# LED_Sheet.net
KiCad netlist of a schematic drawn in Altium Designer
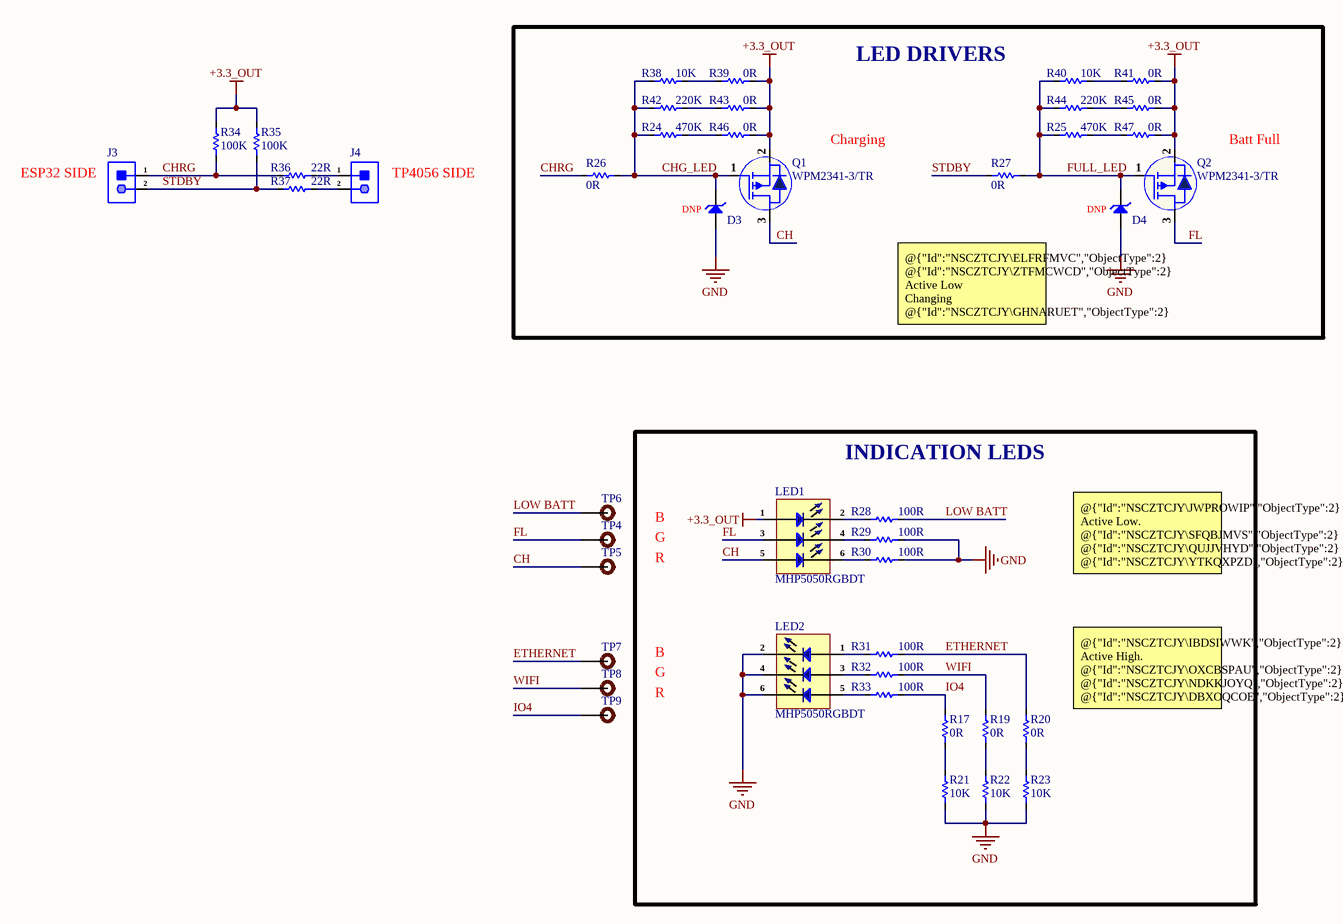
[diagram p0: LED_Sheet.SchDoc]

(export (version "E")
  (design (tool "Eeschema 10.0.6"))
  (components
    (comp (ref "D3")
      (value "MM3Z3V3")
      (footprint "SOD-323")
      (description "±5% Single 3.1V~3.5V 300mW 3.3V SOD-323 Zener Diodes ROHS")
      (fields (field (name "MANUFACTURER") "JSMSEMI") (field (name "LCSC PART NUMBER") "C123917"))
      (libsource (lib "eSpark Libraries") (part "MM3Z3V3"))
    )
    (comp (ref "D4")
      (value "MM3Z3V3")
      (footprint "SOD-323")
      (description "±5% Single 3.1V~3.5V 300mW 3.3V SOD-323 Zener Diodes ROHS")
      (fields (field (name "MANUFACTURER") "JSMSEMI") (field (name "LCSC PART NUMBER") "C123917"))
      (libsource (lib "eSpark Libraries") (part "MM3Z3V3"))
    )
    (comp (ref "J3")
      (value "826629-2")
      (footprint "HDR1X2_")
      (description "CONN HEADER VERT 2POS 2.54MM")
      (fields
        (field (name "MANUFACTURER") "TE Connectivity")
        (field (name "MANUFACTURER PART NUMBER") "8266292")
      )
      (libsource (lib "") (part "826629-2_1"))
    )
    (comp (ref "J4")
      (value "826629-2")
      (footprint "HDR1X2_")
      (description "CONN HEADER VERT 2POS 2.54MM")
      (fields
        (field (name "MANUFACTURER") "TE Connectivity")
        (field (name "MANUFACTURER PART NUMBER") "8266292")
      )
      (libsource (lib "eSpark Libraries") (part "826629-2"))
    )
    (comp (ref "LED1")
      (value "MHP5050RGBDT")
      (footprint "MHP5050RGBDT")
      (description "20mA White Diffused -40℃~+85℃ RGB SMD5050 Light Emitting Diodes (LED) ROHS")
      (fields (field (name "MANUFACTURER") "MEIHUA") (field (name "LCSC PART NUMBER") "C409780"))
      (libsource (lib "eSpark Libraries") (part "MHP5050RGBDT"))
    )
    (comp (ref "LED2")
      (value "MHP5050RGBDT")
      (footprint "MHP5050RGBDT")
      (description "20mA White Diffused -40℃~+85℃ RGB SMD5050 Light Emitting Diodes (LED) ROHS")
      (fields (field (name "MANUFACTURER") "MEIHUA") (field (name "LCSC PART NUMBER") "C409780"))
      (libsource (lib "") (part "MHP5050RGBDT_1"))
    )
    (comp (ref "Q1")
      (value "WPM2341-3/TR")
      (footprint "Sot-23")
      (description "20V 3.5A 750mW 61mΩ@4.5V,3.3A 1V@250uA 1PCSPChannel SOT-23 MOSFETs ROHS")
      (fields (field (name "MANUFACTURER") "WILLSEMI") (field (name "LCSC PART NUMBER") "C167138"))
      (libsource (lib "eSpark Libraries") (part "WPM2341-3/TR"))
    )
    (comp (ref "Q2")
      (value "WPM2341-3/TR")
      (footprint "Sot-23")
      (description "20V 3.5A 750mW 61mΩ@4.5V,3.3A 1V@250uA 1PCSPChannel SOT-23 MOSFETs ROHS")
      (fields (field (name "MANUFACTURER") "WILLSEMI") (field (name "LCSC PART NUMBER") "C167138"))
      (libsource (lib "eSpark Libraries") (part "WPM2341-3/TR"))
    )
    (comp (ref "R17")
      (value "0R")
      (footprint "Res-0402")
      (description "RESISTOR 0402 JUMPER ZERO OHM")
      (fields
        (field (name "MANUFACTURER") "Yageo")
        (field (name "MANUFACTURER PART NUMBER") "AC0402FR-070RL")
      )
      (libsource (lib "eSpark Libraries") (part "AC0402FR-070RL"))
    )
    (comp (ref "R19")
      (value "0R")
      (footprint "Res-0402")
      (description "RESISTOR 0402 JUMPER ZERO OHM")
      (fields
        (field (name "MANUFACTURER") "Yageo")
        (field (name "MANUFACTURER PART NUMBER") "AC0402FR-070RL")
      )
      (libsource (lib "eSpark Libraries") (part "AC0402FR-070RL"))
    )
    (comp (ref "R20")
      (value "0R")
      (footprint "Res-0402")
      (description "RESISTOR 0402 JUMPER ZERO OHM")
      (fields
        (field (name "MANUFACTURER") "Yageo")
        (field (name "MANUFACTURER PART NUMBER") "AC0402FR-070RL")
      )
      (libsource (lib "eSpark Libraries") (part "AC0402FR-070RL"))
    )
    (comp (ref "R21")
      (value "10K")
      (footprint "Res-0402")
      (description "RES 10K OHM 1% 1/16W 0402")
      (fields
        (field (name "MANUFACTURER") "Yageo")
        (field (name "MANUFACTURER PART NUMBER") "RC0402FR-0710KL")
      )
      (libsource (lib "eSpark Libraries") (part "RC0402FR-0710KL"))
    )
    (comp (ref "R22")
      (value "10K")
      (footprint "Res-0402")
      (description "RES 10K OHM 1% 1/16W 0402")
      (fields
        (field (name "MANUFACTURER") "Yageo")
        (field (name "MANUFACTURER PART NUMBER") "RC0402FR-0710KL")
      )
      (libsource (lib "eSpark Libraries") (part "RC0402FR-0710KL"))
    )
    (comp (ref "R23")
      (value "10K")
      (footprint "Res-0402")
      (description "RES 10K OHM 1% 1/16W 0402")
      (fields
        (field (name "MANUFACTURER") "Yageo")
        (field (name "MANUFACTURER PART NUMBER") "RC0402FR-0710KL")
      )
      (libsource (lib "eSpark Libraries") (part "RC0402FR-0710KL"))
    )
    (comp (ref "R24")
      (value "470K")
      (footprint "Res-0402")
      (description "RES 470K OHM 1% 1/16W 0402")
      (fields
        (field (name "MANUFACTURER") "Yageo")
        (field (name "MANUFACTURER PART NUMBER") "RC0402FR-07470KL")
      )
      (libsource (lib "eSpark Libraries") (part "RC0402FR-07470KL"))
    )
    (comp (ref "R25")
      (value "470K")
      (footprint "Res-0402")
      (description "RES 470K OHM 1% 1/16W 0402")
      (fields
        (field (name "MANUFACTURER") "Yageo")
        (field (name "MANUFACTURER PART NUMBER") "RC0402FR-07470KL")
      )
      (libsource (lib "eSpark Libraries") (part "RC0402FR-07470KL"))
    )
    (comp (ref "R26")
      (value "0R")
      (footprint "Res-0402")
      (description "RES 0 OHM JUMPER 1/16W 0402")
      (fields
        (field (name "MANUFACTURER") "Yageo")
        (field (name "MANUFACTURER PART NUMBER") "RC0402FR-070RL")
      )
      (libsource (lib "eSpark Libraries") (part "RC0402FR-070RL"))
    )
    (comp (ref "R27")
      (value "0R")
      (footprint "Res-0402")
      (description "RES 0 OHM JUMPER 1/16W 0402")
      (fields
        (field (name "MANUFACTURER") "Yageo")
        (field (name "MANUFACTURER PART NUMBER") "RC0402FR-070RL")
      )
      (libsource (lib "eSpark Libraries") (part "RC0402FR-070RL"))
    )
    (comp (ref "R28")
      (value "100R")
      (footprint "Res-0402")
      (description "RES 100 OHM 1% 1/16W 0402")
      (fields
        (field (name "MANUFACTURER") "Yageo")
        (field (name "MANUFACTURER PART NUMBER") "RC0402FR-07100RL")
      )
      (libsource (lib "eSpark Libraries") (part "RC0402FR-07100RL"))
    )
    (comp (ref "R29")
      (value "100R")
      (footprint "Res-0402")
      (description "RES 100 OHM 1% 1/16W 0402")
      (fields
        (field (name "MANUFACTURER") "Yageo")
        (field (name "MANUFACTURER PART NUMBER") "RC0402FR-07100RL")
      )
      (libsource (lib "eSpark Libraries") (part "RC0402FR-07100RL"))
    )
    (comp (ref "R30")
      (value "100R")
      (footprint "Res-0402")
      (description "RES 100 OHM 1% 1/16W 0402")
      (fields
        (field (name "MANUFACTURER") "Yageo")
        (field (name "MANUFACTURER PART NUMBER") "RC0402FR-07100RL")
      )
      (libsource (lib "eSpark Libraries") (part "RC0402FR-07100RL"))
    )
    (comp (ref "R31")
      (value "100R")
      (footprint "Res-0402")
      (description "RES 100 OHM 1% 1/16W 0402")
      (fields
        (field (name "MANUFACTURER") "Yageo")
        (field (name "MANUFACTURER PART NUMBER") "RC0402FR-07100RL")
      )
      (libsource (lib "eSpark Libraries") (part "RC0402FR-07100RL"))
    )
    (comp (ref "R32")
      (value "100R")
      (footprint "Res-0402")
      (description "RES 100 OHM 1% 1/16W 0402")
      (fields
        (field (name "MANUFACTURER") "Yageo")
        (field (name "MANUFACTURER PART NUMBER") "RC0402FR-07100RL")
      )
      (libsource (lib "eSpark Libraries") (part "RC0402FR-07100RL"))
    )
    (comp (ref "R33")
      (value "100R")
      (footprint "Res-0402")
      (description "RES 100 OHM 1% 1/16W 0402")
      (fields
        (field (name "MANUFACTURER") "Yageo")
        (field (name "MANUFACTURER PART NUMBER") "RC0402FR-07100RL")
      )
      (libsource (lib "eSpark Libraries") (part "RC0402FR-07100RL"))
    )
    (comp (ref "R34")
      (value "100K")
      (footprint "Res-0402")
      (description "RES 100K OHM 1% 1/16W 0402")
      (fields
        (field (name "MANUFACTURER") "Yageo")
        (field (name "MANUFACTURER PART NUMBER") "RC0402FR-07100KL")
      )
      (libsource (lib "eSpark Libraries") (part "RC0402FR-07100KL"))
    )
    (comp (ref "R35")
      (value "100K")
      (footprint "Res-0402")
      (description "RES 100K OHM 1% 1/16W 0402")
      (fields
        (field (name "MANUFACTURER") "Yageo")
        (field (name "MANUFACTURER PART NUMBER") "RC0402FR-07100KL")
      )
      (libsource (lib "eSpark Libraries") (part "RC0402FR-07100KL"))
    )
    (comp (ref "R36")
      (value "22R")
      (footprint "Res-0402")
      (description "RES 22 OHM 1% 1/16W 0402")
      (fields
        (field (name "MANUFACTURER") "Yageo")
        (field (name "MANUFACTURER PART NUMBER") "RC0402FR-0722RL")
      )
      (libsource (lib "eSpark Libraries") (part "RC0402FR-0722RL"))
    )
    (comp (ref "R37")
      (value "22R")
      (footprint "Res-0402")
      (description "RES 22 OHM 1% 1/16W 0402")
      (fields
        (field (name "MANUFACTURER") "Yageo")
        (field (name "MANUFACTURER PART NUMBER") "RC0402FR-0722RL")
      )
      (libsource (lib "eSpark Libraries") (part "RC0402FR-0722RL"))
    )
    (comp (ref "R38")
      (value "10K")
      (footprint "Res-0402")
      (description "RES 10K OHM 1% 1/16W 0402")
      (fields
        (field (name "MANUFACTURER") "Yageo")
        (field (name "MANUFACTURER PART NUMBER") "RC0402FR-0710KL")
      )
      (libsource (lib "eSpark Libraries") (part "RC0402FR-0710KL"))
    )
    (comp (ref "R39")
      (value "0R")
      (footprint "Res-0402")
      (description "RESISTOR 0402 JUMPER ZERO OHM")
      (fields
        (field (name "MANUFACTURER") "Yageo")
        (field (name "MANUFACTURER PART NUMBER") "AC0402FR-070RL")
      )
      (libsource (lib "eSpark Libraries") (part "AC0402FR-070RL"))
    )
    (comp (ref "R40")
      (value "10K")
      (footprint "Res-0402")
      (description "RES 10K OHM 1% 1/16W 0402")
      (fields
        (field (name "MANUFACTURER") "Yageo")
        (field (name "MANUFACTURER PART NUMBER") "RC0402FR-0710KL")
      )
      (libsource (lib "eSpark Libraries") (part "RC0402FR-0710KL"))
    )
    (comp (ref "R41")
      (value "0R")
      (footprint "Res-0402")
      (description "RESISTOR 0402 JUMPER ZERO OHM")
      (fields
        (field (name "MANUFACTURER") "Yageo")
        (field (name "MANUFACTURER PART NUMBER") "AC0402FR-070RL")
      )
      (libsource (lib "eSpark Libraries") (part "AC0402FR-070RL"))
    )
    (comp (ref "R42")
      (value "220K")
      (footprint "Res-0402")
      (description "RES 220K OHM 1% 1/16W 0402")
      (fields
        (field (name "MANUFACTURER") "Yageo")
        (field (name "MANUFACTURER PART NUMBER") "RC0402FR-07220KL")
      )
      (libsource (lib "eSpark Libraries") (part "RC0402FR-07220KL"))
    )
    (comp (ref "R43")
      (value "0R")
      (footprint "Res-0402")
      (description "RESISTOR 0402 JUMPER ZERO OHM")
      (fields
        (field (name "MANUFACTURER") "Yageo")
        (field (name "MANUFACTURER PART NUMBER") "AC0402FR-070RL")
      )
      (libsource (lib "eSpark Libraries") (part "AC0402FR-070RL"))
    )
    (comp (ref "R44")
      (value "220K")
      (footprint "Res-0402")
      (description "RES 220K OHM 1% 1/16W 0402")
      (fields
        (field (name "MANUFACTURER") "Yageo")
        (field (name "MANUFACTURER PART NUMBER") "RC0402FR-07220KL")
      )
      (libsource (lib "eSpark Libraries") (part "RC0402FR-07220KL"))
    )
    (comp (ref "R45")
      (value "0R")
      (footprint "Res-0402")
      (description "RESISTOR 0402 JUMPER ZERO OHM")
      (fields
        (field (name "MANUFACTURER") "Yageo")
        (field (name "MANUFACTURER PART NUMBER") "AC0402FR-070RL")
      )
      (libsource (lib "eSpark Libraries") (part "AC0402FR-070RL"))
    )
    (comp (ref "R46")
      (value "0R")
      (footprint "Res-0402")
      (description "RESISTOR 0402 JUMPER ZERO OHM")
      (fields
        (field (name "MANUFACTURER") "Yageo")
        (field (name "MANUFACTURER PART NUMBER") "AC0402FR-070RL")
      )
      (libsource (lib "eSpark Libraries") (part "AC0402FR-070RL"))
    )
    (comp (ref "R47")
      (value "0R")
      (footprint "Res-0402")
      (description "RESISTOR 0402 JUMPER ZERO OHM")
      (fields
        (field (name "MANUFACTURER") "Yageo")
        (field (name "MANUFACTURER PART NUMBER") "AC0402FR-070RL")
      )
      (libsource (lib "eSpark Libraries") (part "AC0402FR-070RL"))
    )
    (comp (ref "TP4")
      (value "TEST POINT 0.5mm Dia")
      (footprint "Test-point - 0.5mm")
      (description "Test Point ON")
      (libsource (lib "eSpark Libraries") (part "TEST POINT 0.5mm Dia"))
    )
    (comp (ref "TP5")
      (value "TEST POINT 0.5mm Dia")
      (footprint "Test-point - 0.5mm")
      (description "Test Point ON")
      (libsource (lib "eSpark Libraries") (part "TEST POINT 0.5mm Dia"))
    )
    (comp (ref "TP6")
      (value "TEST POINT 0.5mm Dia")
      (footprint "Test-point - 0.5mm")
      (description "Test Point ON")
      (libsource (lib "eSpark Libraries") (part "TEST POINT 0.5mm Dia"))
    )
    (comp (ref "TP7")
      (value "TEST POINT 0.5mm Dia")
      (footprint "Test-point - 0.5mm")
      (description "Test Point ON")
      (libsource (lib "eSpark Libraries") (part "TEST POINT 0.5mm Dia"))
    )
    (comp (ref "TP8")
      (value "TEST POINT 0.5mm Dia")
      (footprint "Test-point - 0.5mm")
      (description "Test Point ON")
      (libsource (lib "eSpark Libraries") (part "TEST POINT 0.5mm Dia"))
    )
    (comp (ref "TP9")
      (value "TEST POINT 0.5mm Dia")
      (footprint "Test-point - 0.5mm")
      (description "Test Point ON")
      (libsource (lib "eSpark Libraries") (part "TEST POINT 0.5mm Dia"))
    )
  )
  (nets
    (net (code "1") (name "+3.3_OUT") (class "Default")
      (node (ref "LED1") (pin "1") (pinfunction "1_1") (pintype "passive"))
      (node (ref "Q1") (pin "2") (pinfunction "S_2") (pintype "passive"))
      (node (ref "Q2") (pin "2") (pinfunction "S_2") (pintype "passive"))
      (node (ref "R34") (pin "2") (pinfunction "2_2") (pintype "passive"))
      (node (ref "R35") (pin "2") (pinfunction "2_2") (pintype "passive"))
      (node (ref "R39") (pin "1") (pinfunction "1_1") (pintype "passive"))
      (node (ref "R41") (pin "1") (pinfunction "1_1") (pintype "passive"))
      (node (ref "R43") (pin "1") (pinfunction "1_1") (pintype "passive"))
      (node (ref "R45") (pin "1") (pinfunction "1_1") (pintype "passive"))
      (node (ref "R46") (pin "1") (pinfunction "1_1") (pintype "passive"))
      (node (ref "R47") (pin "1") (pinfunction "1_1") (pintype "passive"))
    )
    (net (code "2") (name "/CH") (class "Default")
      (node (ref "LED1") (pin "5") (pinfunction "5_5") (pintype "passive"))
      (node (ref "Q1") (pin "3") (pinfunction "D_3") (pintype "passive"))
      (node (ref "TP5") (pin "1") (pinfunction "1_1") (pintype "passive"))
    )
    (net (code "3") (name "/CHG_LED") (class "Default")
      (node (ref "D3") (pin "1") (pinfunction "K_1") (pintype "passive"))
      (node (ref "Q1") (pin "1") (pinfunction "G_1") (pintype "passive"))
      (node (ref "R24") (pin "1") (pinfunction "1_1") (pintype "passive"))
      (node (ref "R26") (pin "2") (pinfunction "2_2") (pintype "passive"))
      (node (ref "R38") (pin "2") (pinfunction "2_2") (pintype "passive"))
      (node (ref "R42") (pin "1") (pinfunction "1_1") (pintype "passive"))
    )
    (net (code "4") (name "/CHRG") (class "Default")
      (node (ref "J3") (pin "1") (pinfunction "1_1") (pintype "passive"))
      (node (ref "R26") (pin "1") (pinfunction "1_1") (pintype "passive"))
      (node (ref "R34") (pin "1") (pinfunction "1_1") (pintype "passive"))
      (node (ref "R36") (pin "1") (pinfunction "1_1") (pintype "passive"))
    )
    (net (code "5") (name "/ETHERNET") (class "Default")
      (node (ref "R20") (pin "2") (pinfunction "2_2") (pintype "passive"))
      (node (ref "R31") (pin "2") (pinfunction "2_2") (pintype "passive"))
      (node (ref "TP7") (pin "1") (pinfunction "1_1") (pintype "passive"))
    )
    (net (code "6") (name "/FL") (class "Default")
      (node (ref "LED1") (pin "3") (pinfunction "3_3") (pintype "passive"))
      (node (ref "Q2") (pin "3") (pinfunction "D_3") (pintype "passive"))
      (node (ref "TP4") (pin "1") (pinfunction "1_1") (pintype "passive"))
    )
    (net (code "7") (name "/FULL_LED") (class "Default")
      (node (ref "D4") (pin "1") (pinfunction "K_1") (pintype "passive"))
      (node (ref "Q2") (pin "1") (pinfunction "G_1") (pintype "passive"))
      (node (ref "R25") (pin "1") (pinfunction "1_1") (pintype "passive"))
      (node (ref "R27") (pin "2") (pinfunction "2_2") (pintype "passive"))
      (node (ref "R40") (pin "2") (pinfunction "2_2") (pintype "passive"))
      (node (ref "R44") (pin "1") (pinfunction "1_1") (pintype "passive"))
    )
    (net (code "8") (name "/IO4") (class "Default")
      (node (ref "R17") (pin "2") (pinfunction "2_2") (pintype "passive"))
      (node (ref "R33") (pin "2") (pinfunction "2_2") (pintype "passive"))
      (node (ref "TP9") (pin "1") (pinfunction "1_1") (pintype "passive"))
    )
    (net (code "9") (name "/LOW BATT") (class "Default")
      (node (ref "R28") (pin "2") (pinfunction "2_2") (pintype "passive"))
      (node (ref "TP6") (pin "1") (pinfunction "1_1") (pintype "passive"))
    )
    (net (code "10") (name "/STDBY") (class "Default")
      (node (ref "J3") (pin "2") (pinfunction "2_2") (pintype "passive"))
      (node (ref "R27") (pin "1") (pinfunction "1_1") (pintype "passive"))
      (node (ref "R35") (pin "1") (pinfunction "1_1") (pintype "passive"))
      (node (ref "R37") (pin "1") (pinfunction "1_1") (pintype "passive"))
    )
    (net (code "11") (name "/WIFI") (class "Default")
      (node (ref "R19") (pin "2") (pinfunction "2_2") (pintype "passive"))
      (node (ref "R32") (pin "2") (pinfunction "2_2") (pintype "passive"))
      (node (ref "TP8") (pin "1") (pinfunction "1_1") (pintype "passive"))
    )
    (net (code "12") (name "GND") (class "Default")
      (node (ref "D3") (pin "2") (pinfunction "A_2") (pintype "passive"))
      (node (ref "D4") (pin "2") (pinfunction "A_2") (pintype "passive"))
      (node (ref "LED2") (pin "2") (pinfunction "2_2") (pintype "passive"))
      (node (ref "LED2") (pin "4") (pinfunction "4_4") (pintype "passive"))
      (node (ref "LED2") (pin "6") (pinfunction "6_6") (pintype "passive"))
      (node (ref "R21") (pin "1") (pinfunction "1_1") (pintype "passive"))
      (node (ref "R22") (pin "1") (pinfunction "1_1") (pintype "passive"))
      (node (ref "R23") (pin "1") (pinfunction "1_1") (pintype "passive"))
      (node (ref "R29") (pin "2") (pinfunction "2_2") (pintype "passive"))
      (node (ref "R30") (pin "2") (pinfunction "2_2") (pintype "passive"))
    )
    (net (code "13") (name "Net-(J4-Pad1)") (class "Default")
      (node (ref "J4") (pin "1") (pinfunction "1_1") (pintype "passive"))
      (node (ref "R36") (pin "2") (pinfunction "2_2") (pintype "passive"))
    )
    (net (code "14") (name "Net-(J4-Pad2)") (class "Default")
      (node (ref "J4") (pin "2") (pinfunction "2_2") (pintype "passive"))
      (node (ref "R37") (pin "2") (pinfunction "2_2") (pintype "passive"))
    )
    (net (code "15") (name "Net-(LED1-Pad2)") (class "Default")
      (node (ref "LED1") (pin "2") (pinfunction "2_2") (pintype "passive"))
      (node (ref "R28") (pin "1") (pinfunction "1_1") (pintype "passive"))
    )
    (net (code "16") (name "Net-(LED1-Pad4)") (class "Default")
      (node (ref "LED1") (pin "4") (pinfunction "4_4") (pintype "passive"))
      (node (ref "R29") (pin "1") (pinfunction "1_1") (pintype "passive"))
    )
    (net (code "17") (name "Net-(LED1-Pad6)") (class "Default")
      (node (ref "LED1") (pin "6") (pinfunction "6_6") (pintype "passive"))
      (node (ref "R30") (pin "1") (pinfunction "1_1") (pintype "passive"))
    )
    (net (code "18") (name "Net-(LED2-Pad1)") (class "Default")
      (node (ref "LED2") (pin "1") (pinfunction "1_1") (pintype "passive"))
      (node (ref "R31") (pin "1") (pinfunction "1_1") (pintype "passive"))
    )
    (net (code "19") (name "Net-(LED2-Pad3)") (class "Default")
      (node (ref "LED2") (pin "3") (pinfunction "3_3") (pintype "passive"))
      (node (ref "R32") (pin "1") (pinfunction "1_1") (pintype "passive"))
    )
    (net (code "20") (name "Net-(LED2-Pad5)") (class "Default")
      (node (ref "LED2") (pin "5") (pinfunction "5_5") (pintype "passive"))
      (node (ref "R33") (pin "1") (pinfunction "1_1") (pintype "passive"))
    )
    (net (code "21") (name "Net-(R17-Pad1)") (class "Default")
      (node (ref "R17") (pin "1") (pinfunction "1_1") (pintype "passive"))
      (node (ref "R21") (pin "2") (pinfunction "2_2") (pintype "passive"))
    )
    (net (code "22") (name "Net-(R19-Pad1)") (class "Default")
      (node (ref "R19") (pin "1") (pinfunction "1_1") (pintype "passive"))
      (node (ref "R22") (pin "2") (pinfunction "2_2") (pintype "passive"))
    )
    (net (code "23") (name "Net-(R20-Pad1)") (class "Default")
      (node (ref "R20") (pin "1") (pinfunction "1_1") (pintype "passive"))
      (node (ref "R23") (pin "2") (pinfunction "2_2") (pintype "passive"))
    )
    (net (code "24") (name "Net-(R24-Pad2)") (class "Default")
      (node (ref "R24") (pin "2") (pinfunction "2_2") (pintype "passive"))
      (node (ref "R46") (pin "2") (pinfunction "2_2") (pintype "passive"))
    )
    (net (code "25") (name "Net-(R25-Pad2)") (class "Default")
      (node (ref "R25") (pin "2") (pinfunction "2_2") (pintype "passive"))
      (node (ref "R47") (pin "2") (pinfunction "2_2") (pintype "passive"))
    )
    (net (code "26") (name "Net-(R38-Pad1)") (class "Default")
      (node (ref "R38") (pin "1") (pinfunction "1_1") (pintype "passive"))
      (node (ref "R39") (pin "2") (pinfunction "2_2") (pintype "passive"))
    )
    (net (code "27") (name "Net-(R40-Pad1)") (class "Default")
      (node (ref "R40") (pin "1") (pinfunction "1_1") (pintype "passive"))
      (node (ref "R41") (pin "2") (pinfunction "2_2") (pintype "passive"))
    )
    (net (code "28") (name "Net-(R42-Pad2)") (class "Default")
      (node (ref "R42") (pin "2") (pinfunction "2_2") (pintype "passive"))
      (node (ref "R43") (pin "2") (pinfunction "2_2") (pintype "passive"))
    )
    (net (code "29") (name "Net-(R44-Pad2)") (class "Default")
      (node (ref "R44") (pin "2") (pinfunction "2_2") (pintype "passive"))
      (node (ref "R45") (pin "2") (pinfunction "2_2") (pintype "passive"))
    )
  )
)
